# LandCruiser-Controller_1V1.net
KiCad netlist of a schematic drawn in EAGLE
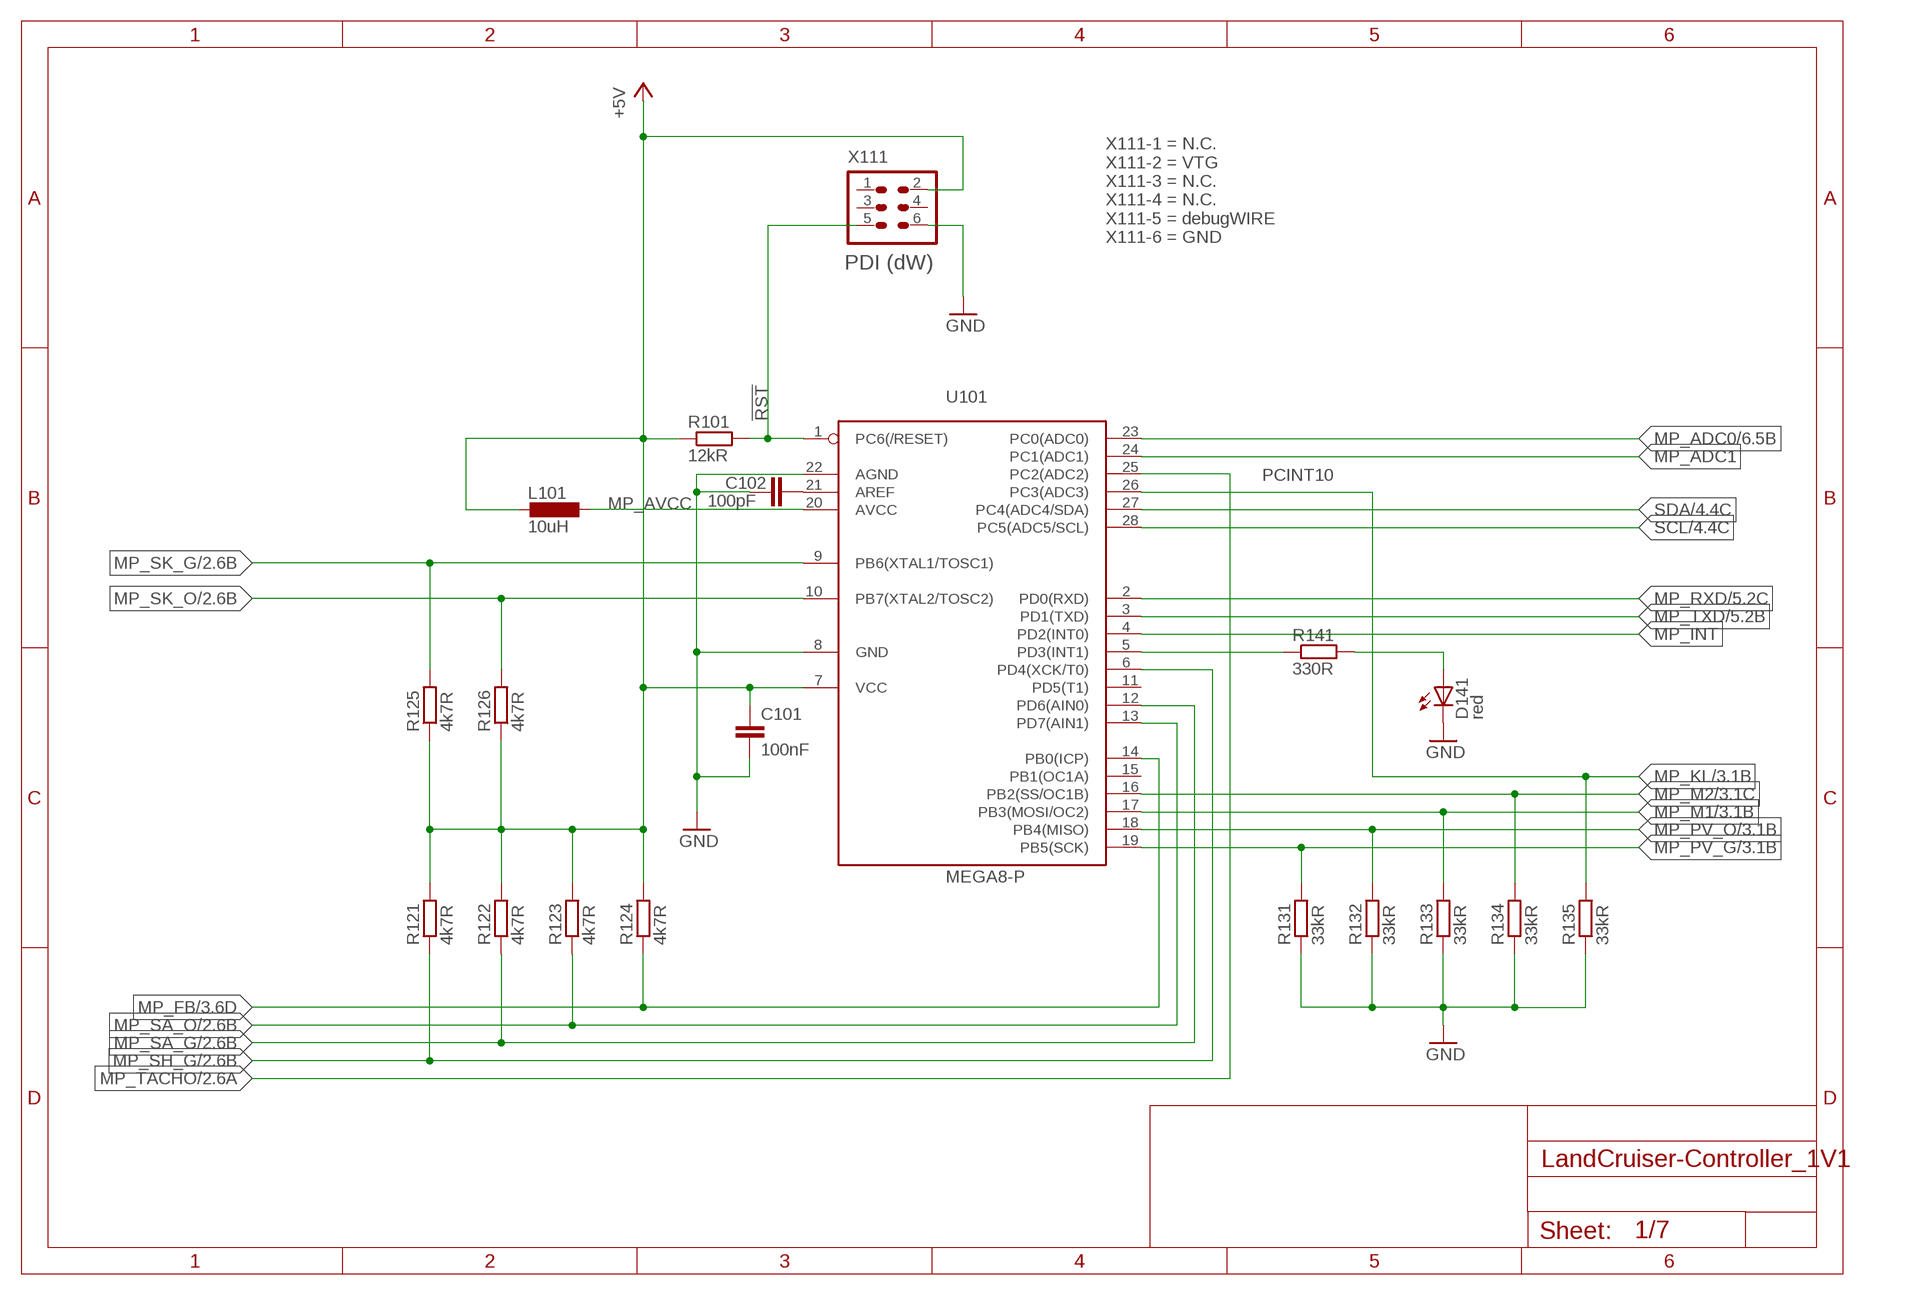
[diagram p0: schematic, sheet 1]
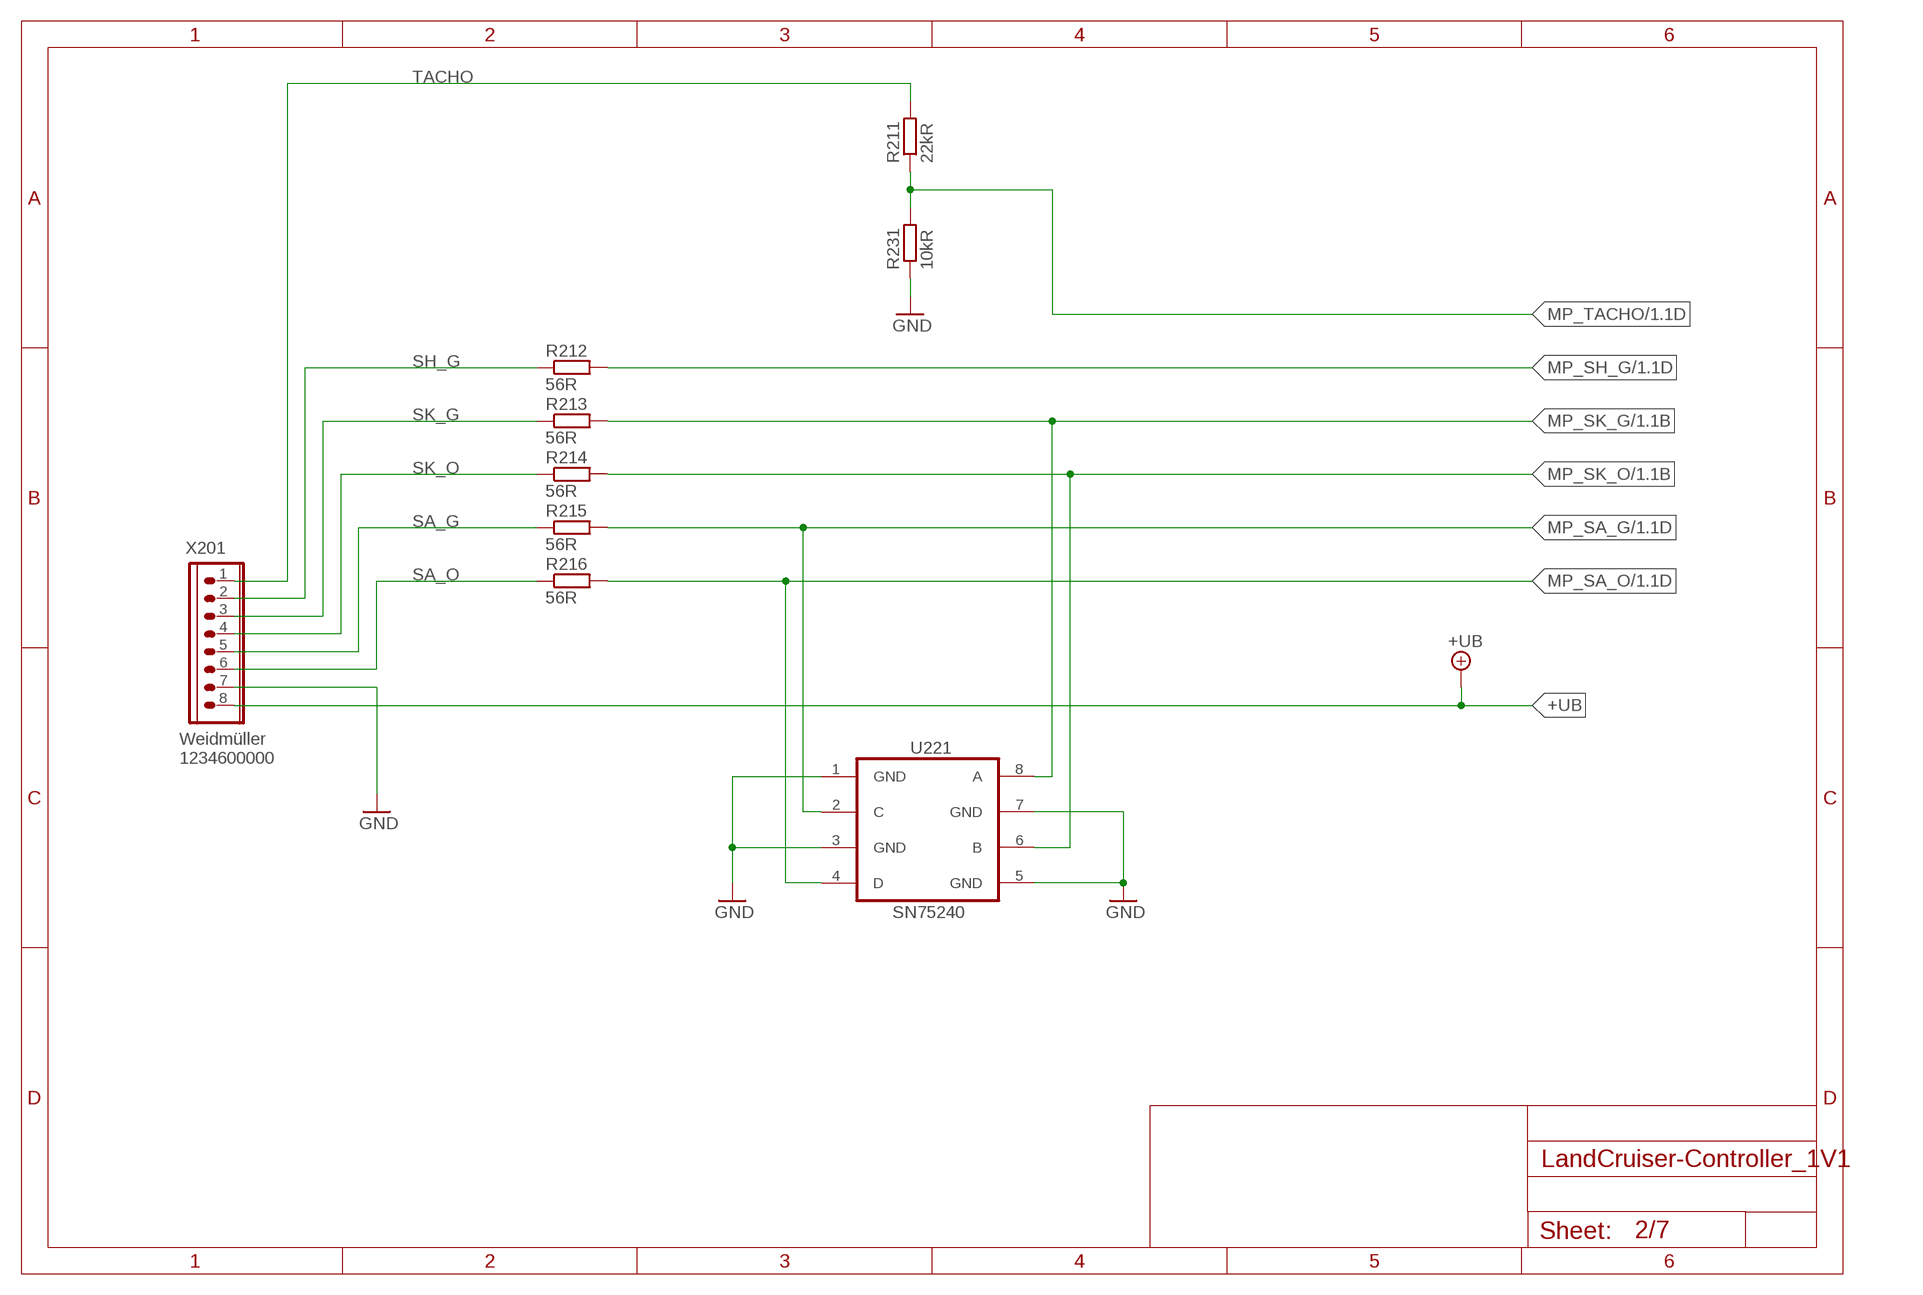
[diagram p1: schematic, sheet 2]
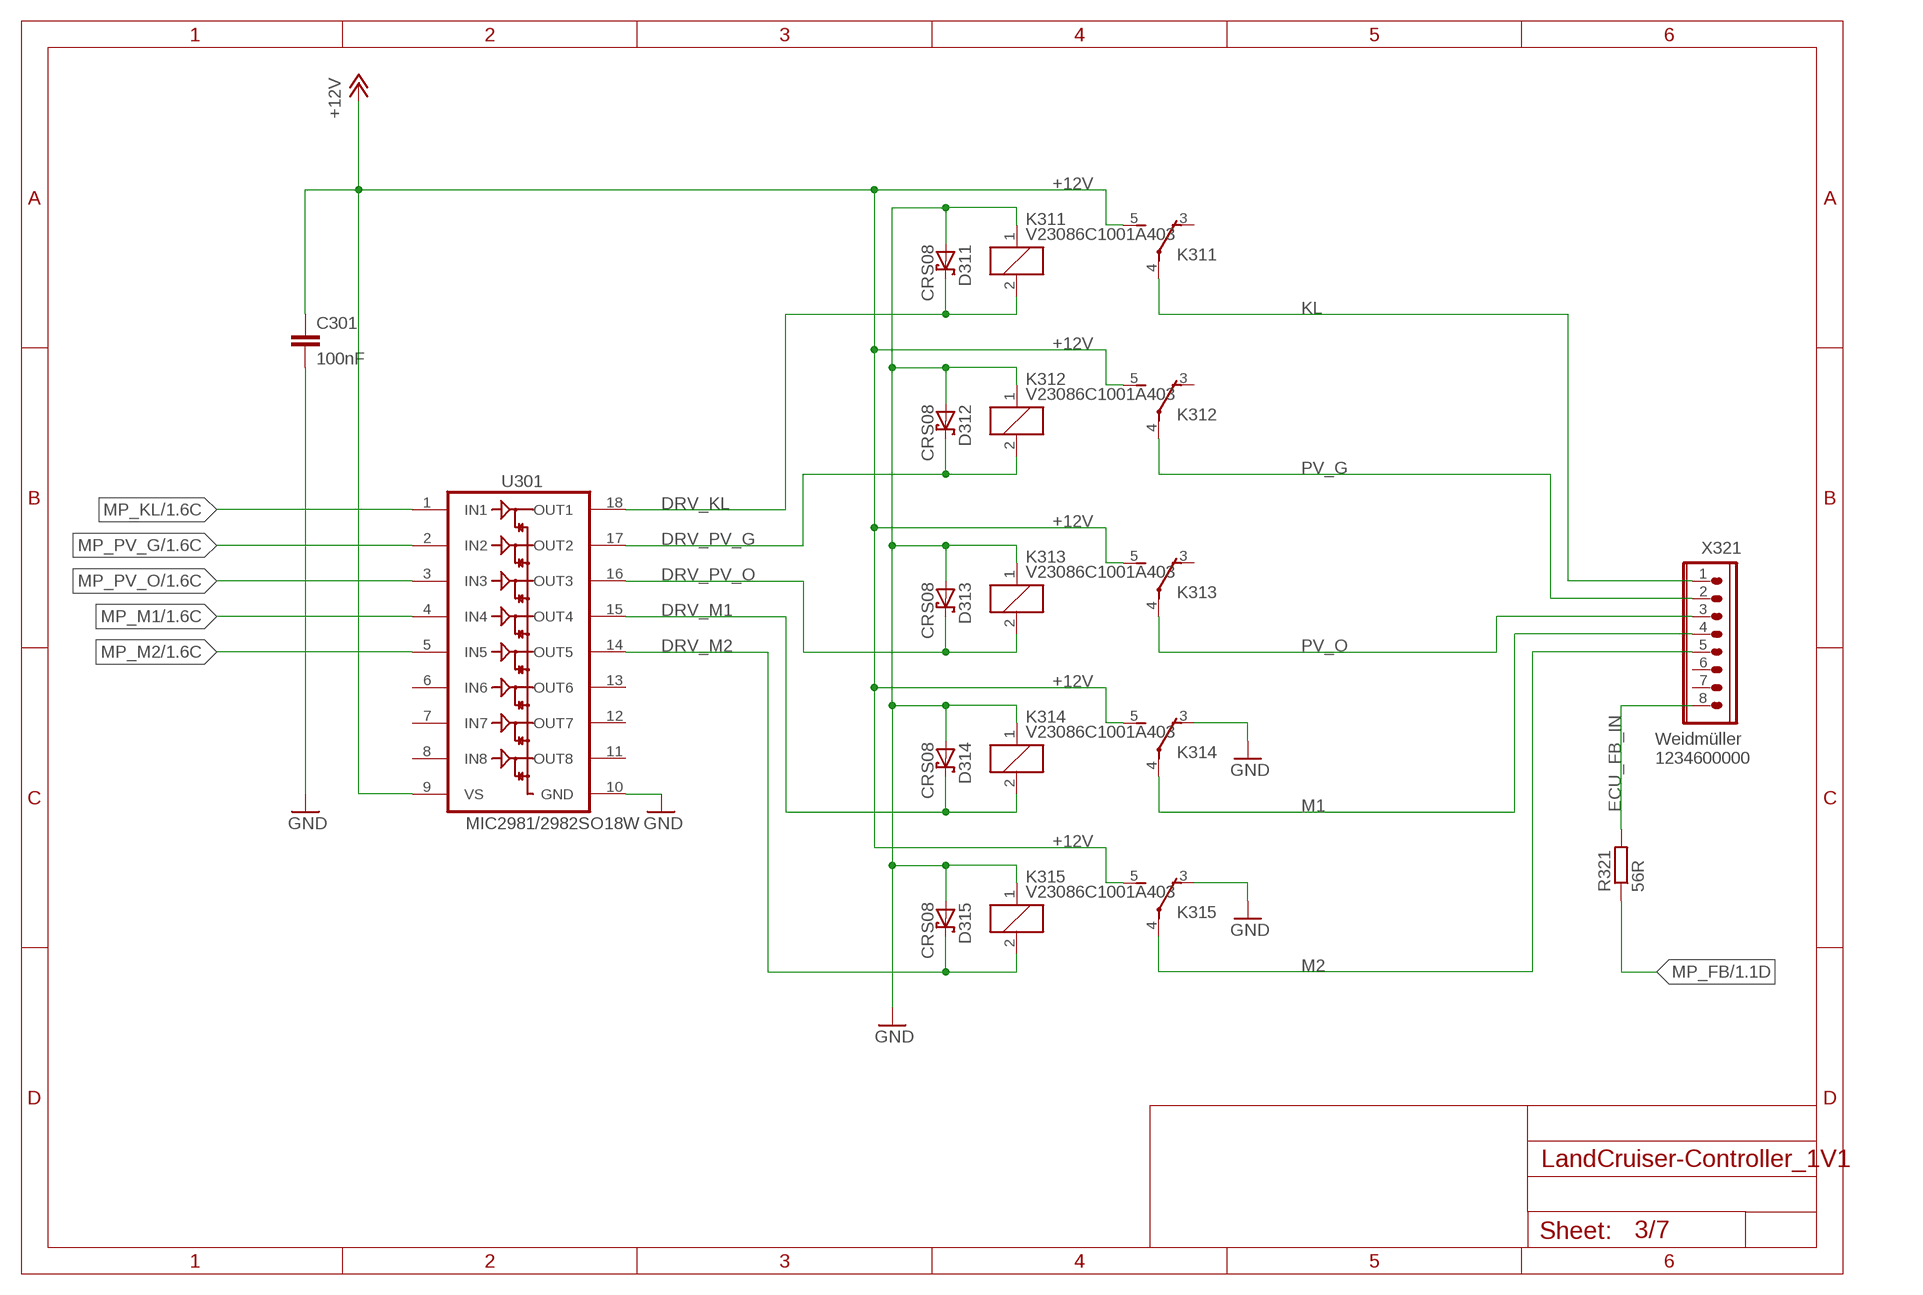
[diagram p2: schematic, sheet 3]
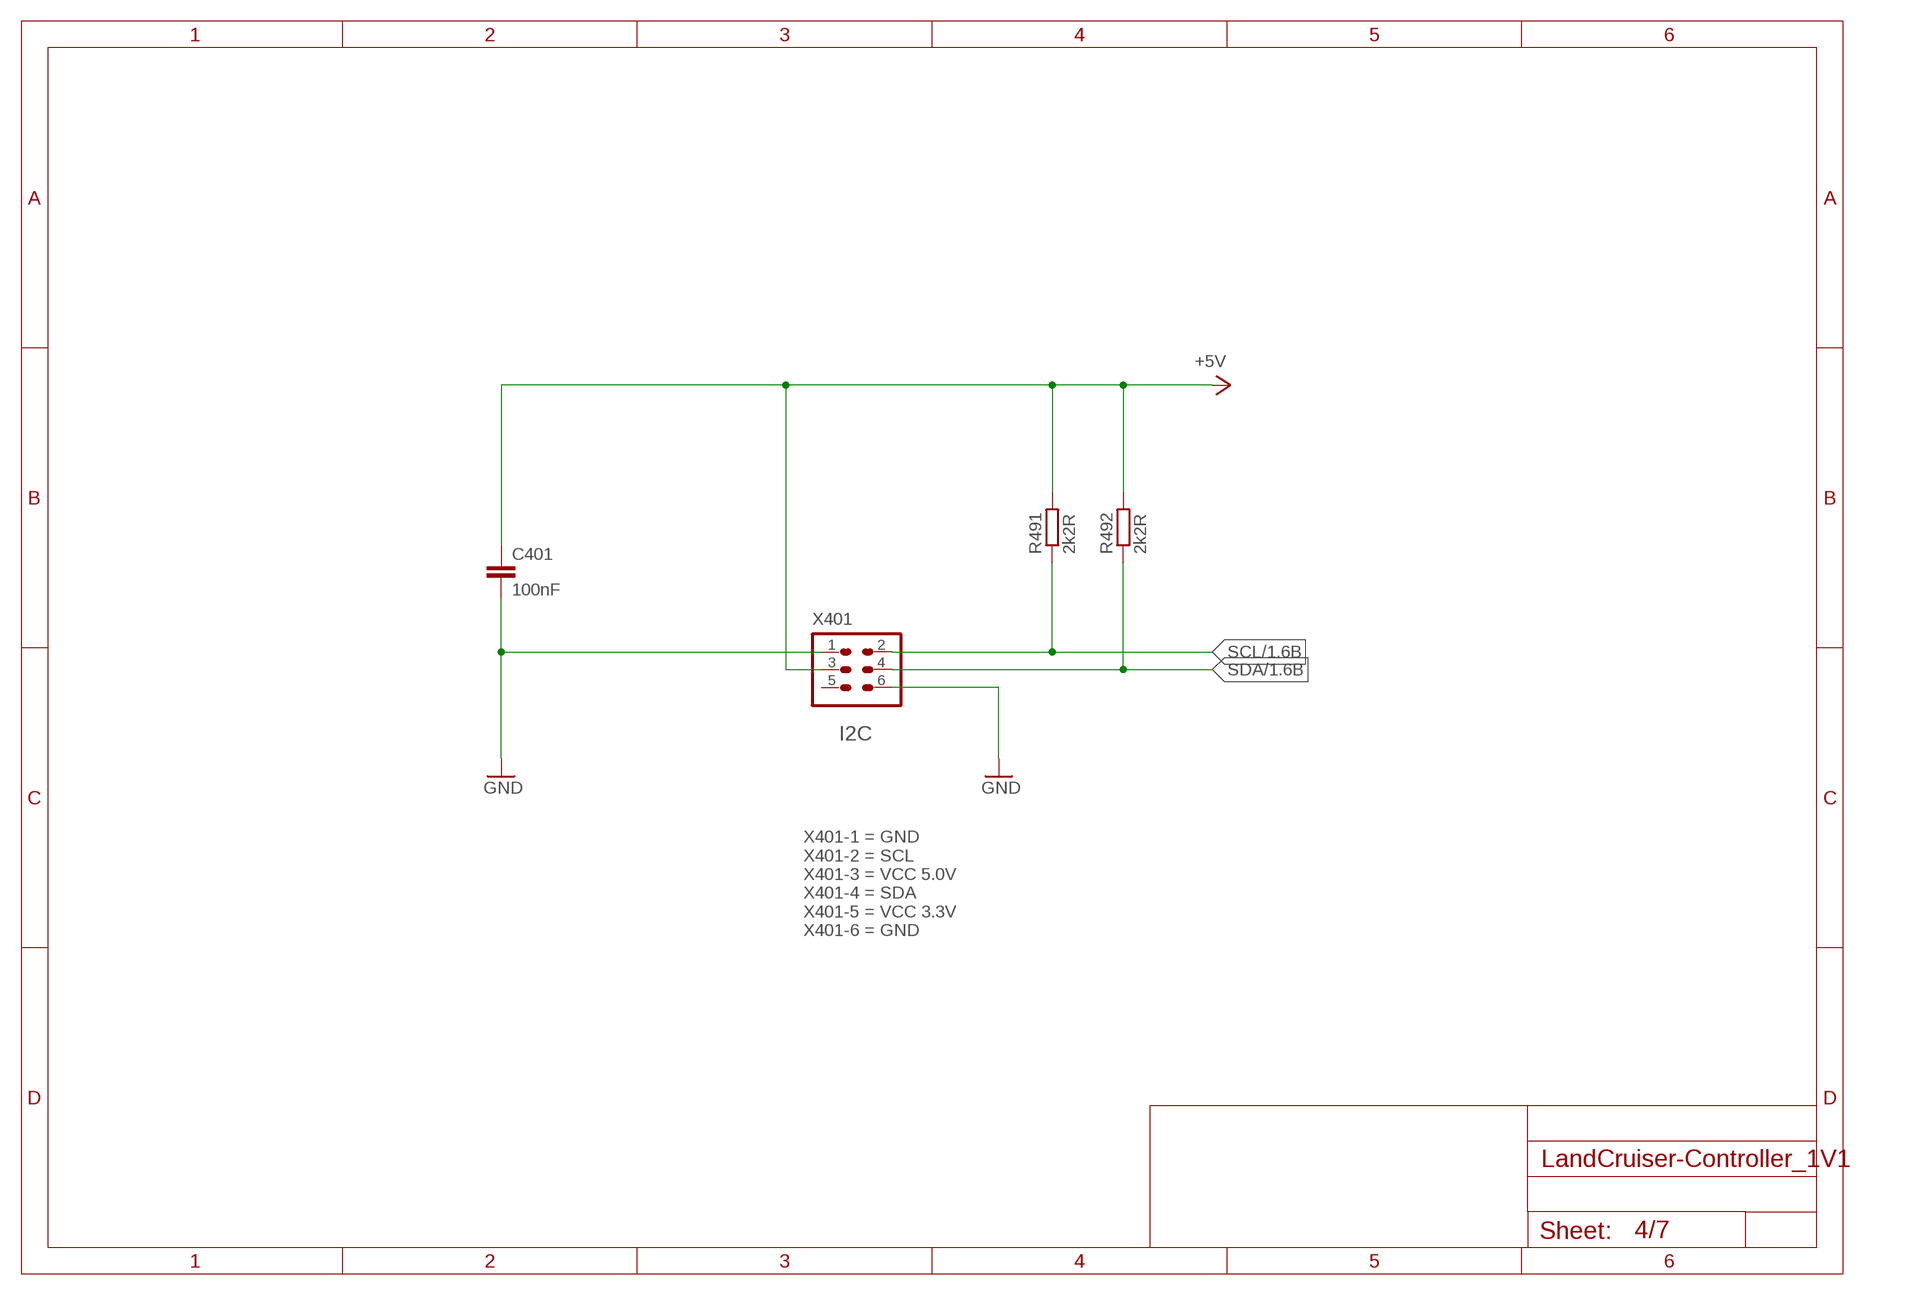
[diagram p3: schematic, sheet 4]
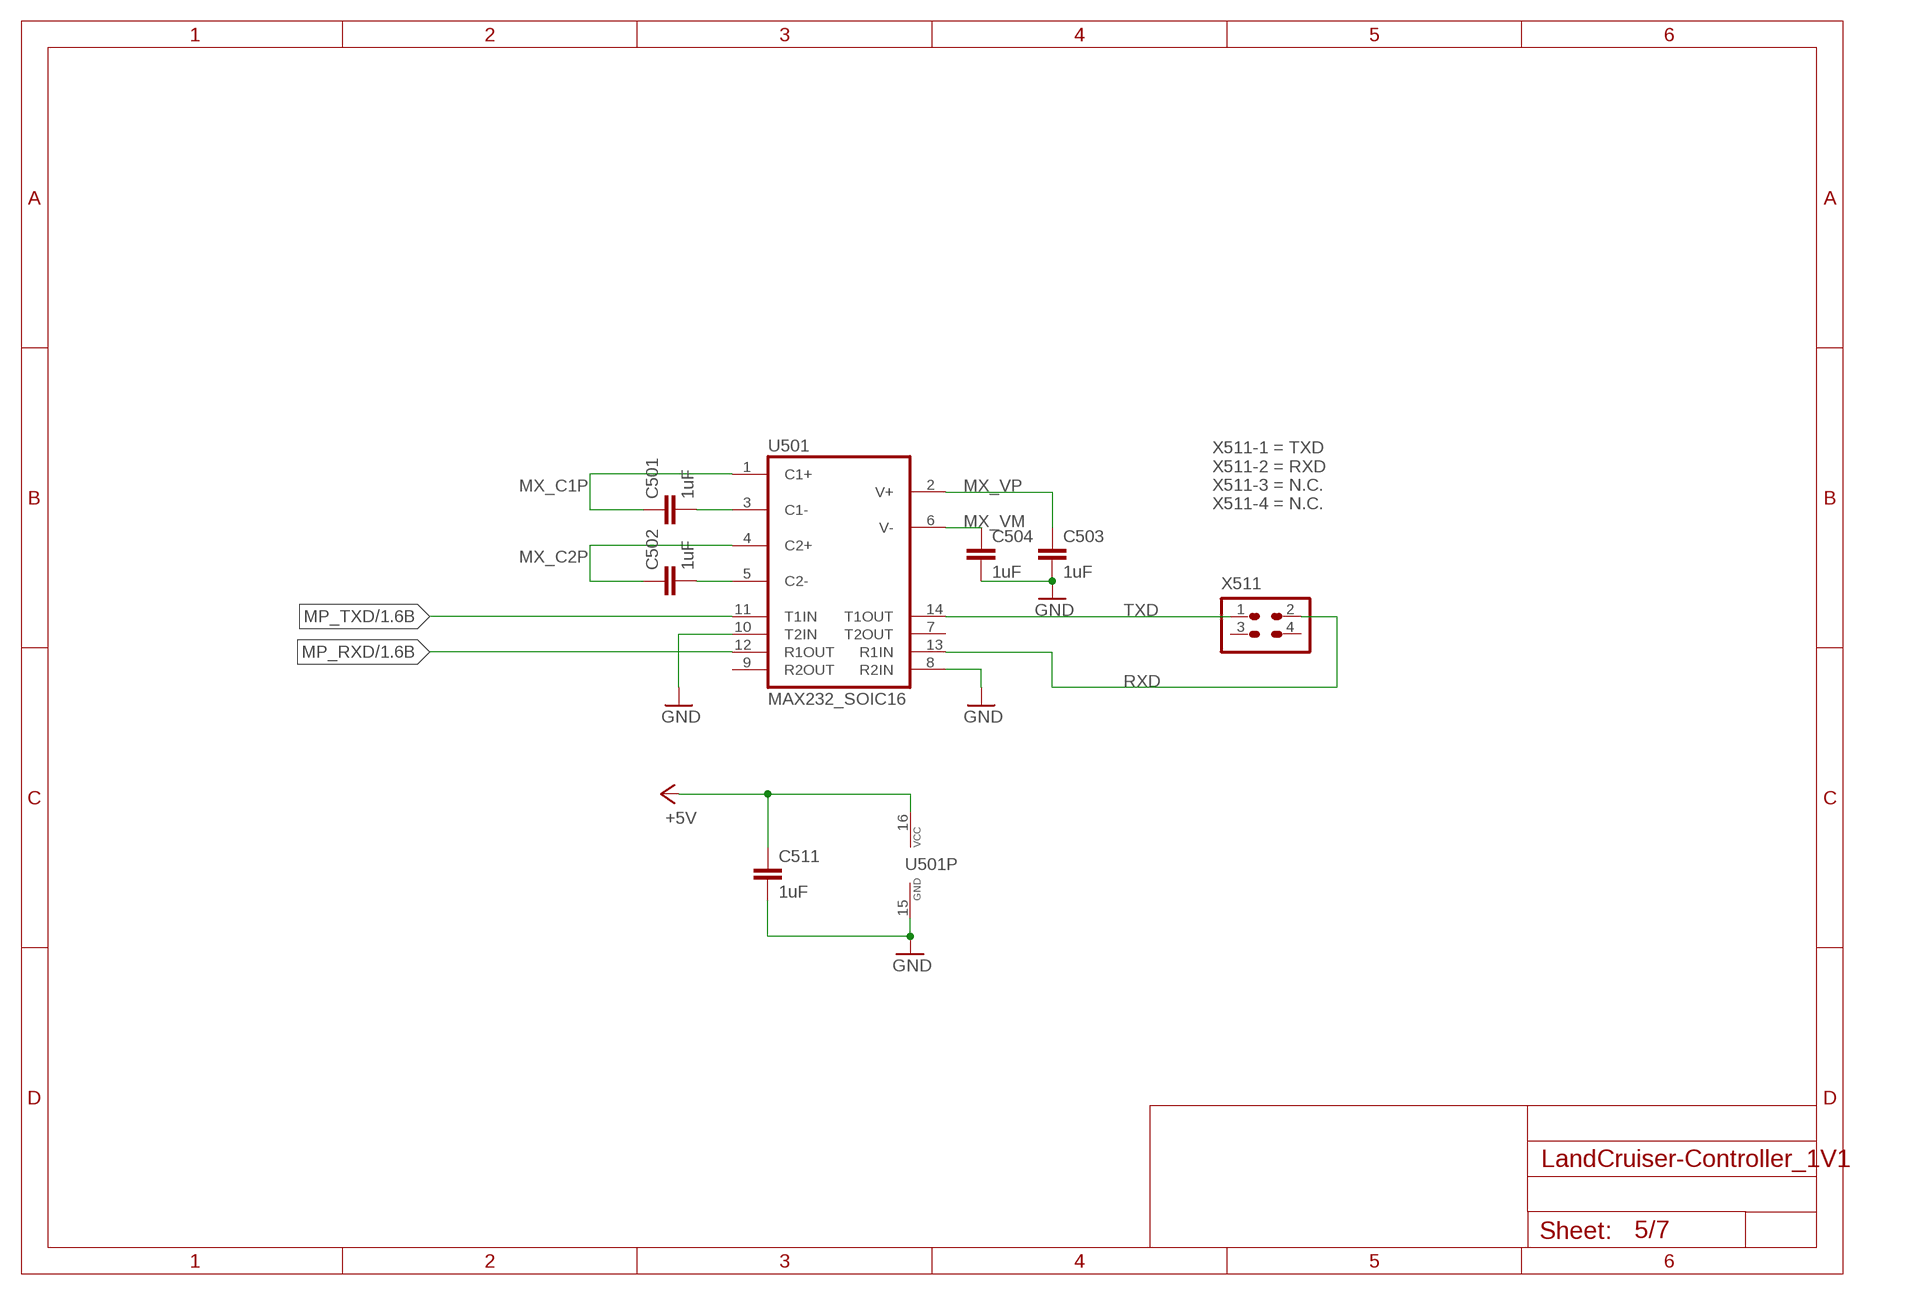
[diagram p4: schematic, sheet 5]
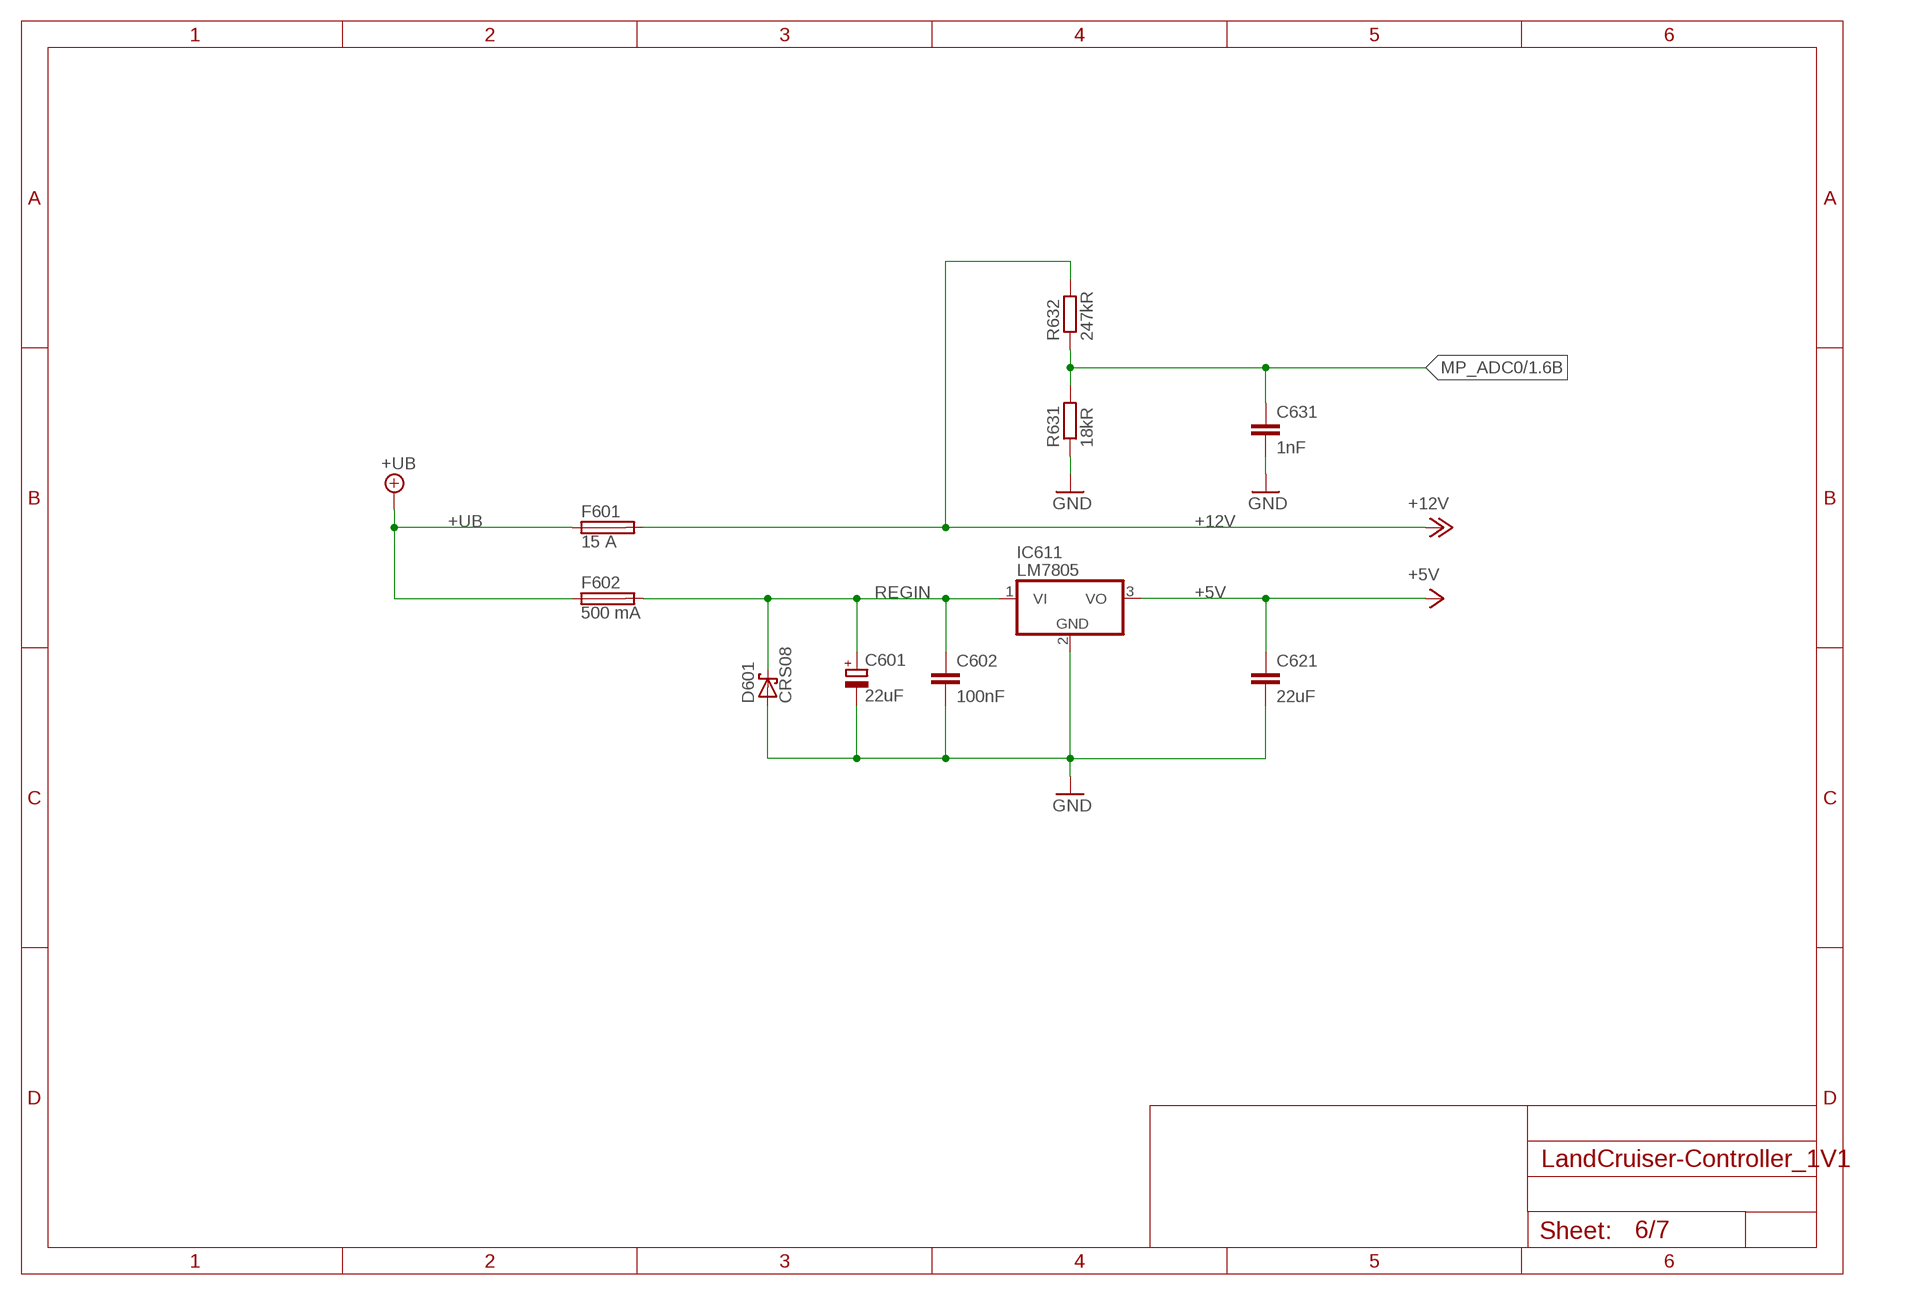
[diagram p5: schematic, sheet 6]
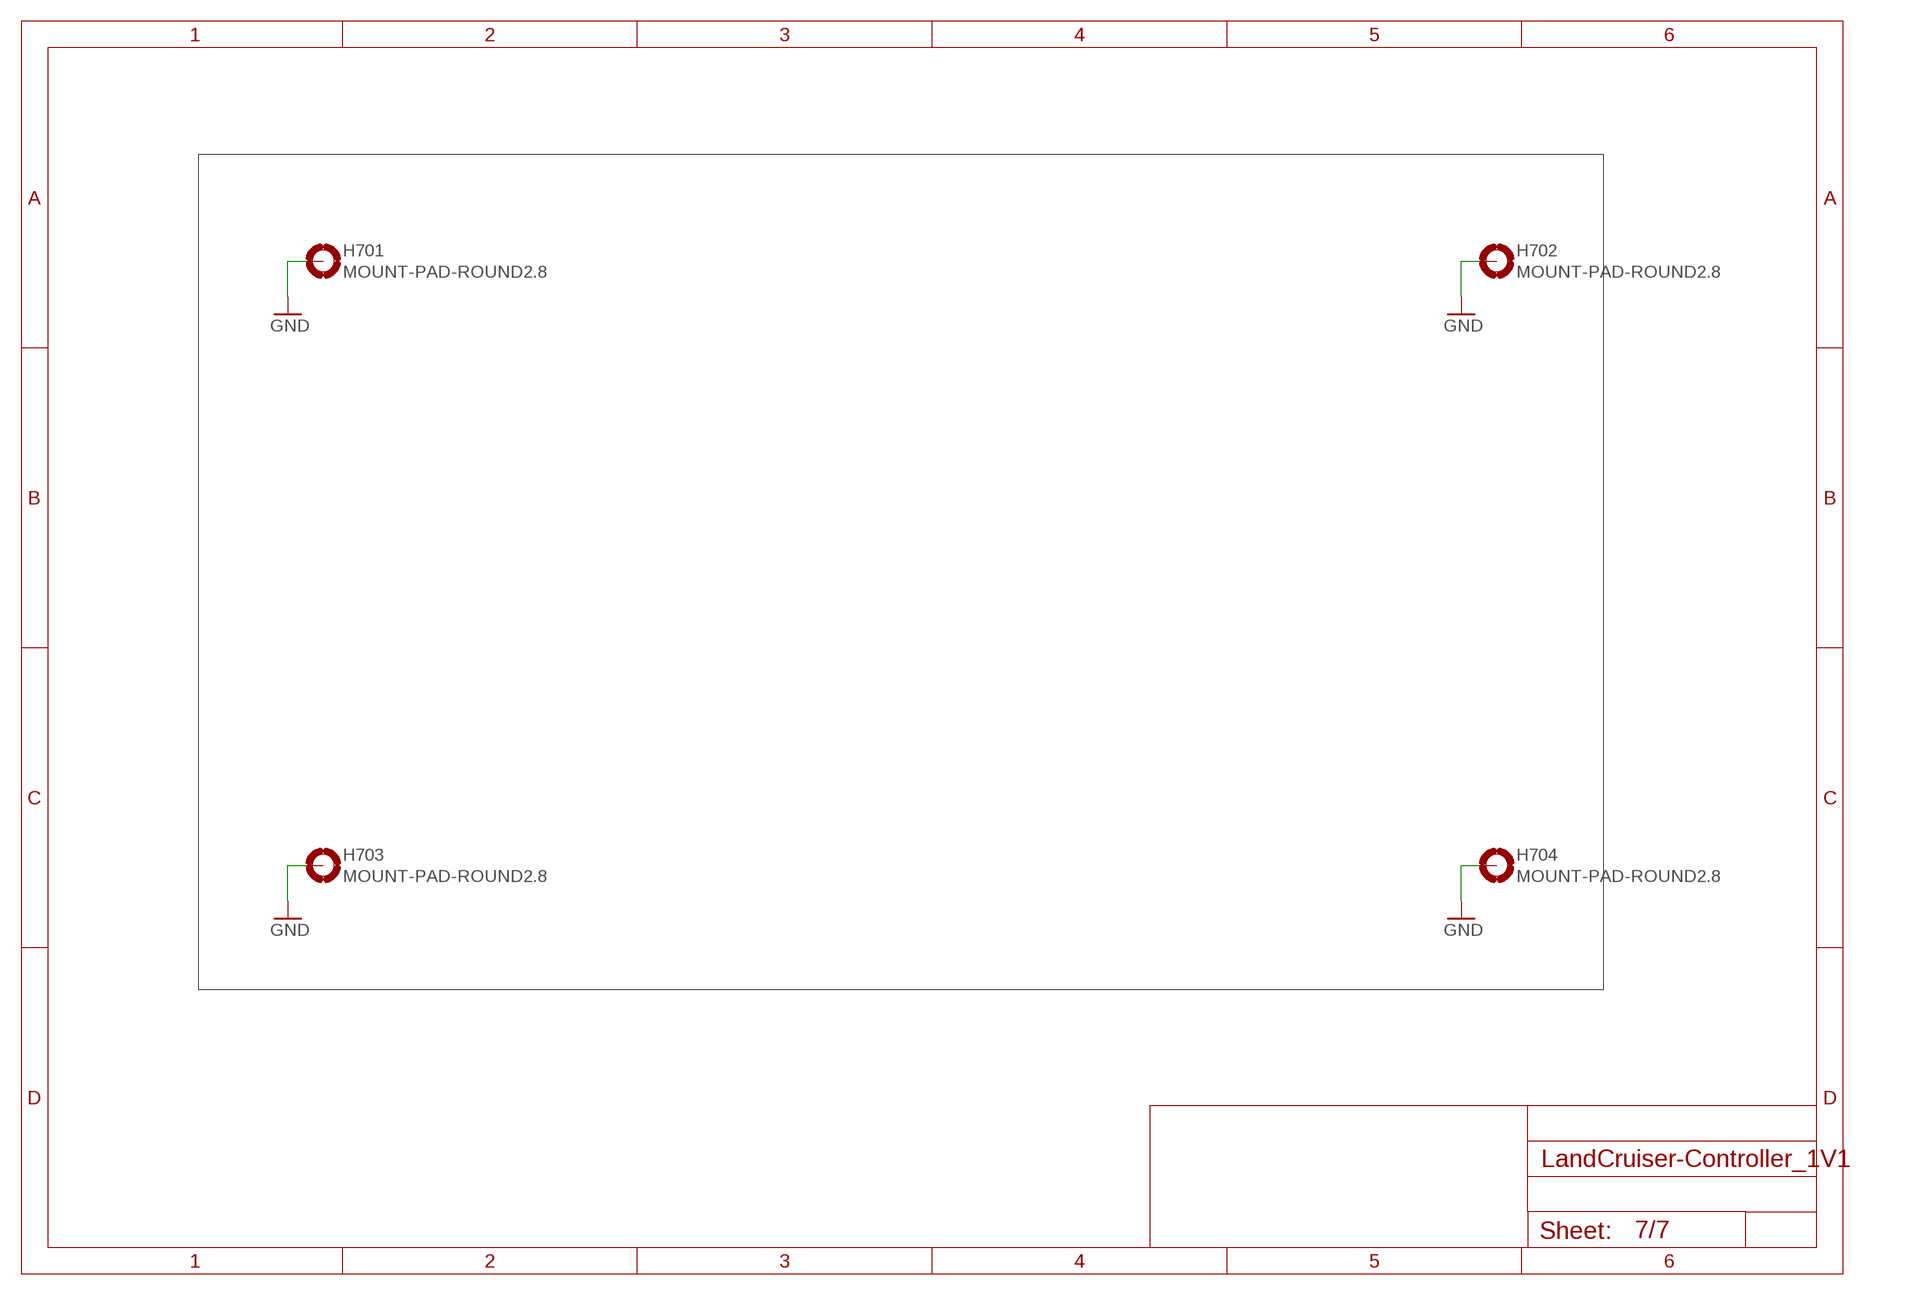
[diagram p6: schematic, sheet 7]

(export (version "E")
  (design (tool "Eeschema 10.0.6"))
  (components
    (comp (ref "C401")
      (value "100nF")
      (footprint "eagle-import:C0805")
      (libsource (lib "eagle-import") (part "C-EUC0805"))
    )
    (comp (ref "R491")
      (value "2k2R")
      (footprint "eagle-import:R0805")
      (libsource (lib "eagle-import") (part "R-EU_R0805"))
    )
    (comp (ref "R492")
      (value "2k2R")
      (footprint "eagle-import:R0805")
      (libsource (lib "eagle-import") (part "R-EU_R0805"))
    )
    (comp (ref "X401")
      (value "I2C")
      (footprint "eagle-import:2X03")
      (libsource (lib "eagle-import") (part "HEADER-2X3"))
    )
    (comp (ref "C301")
      (value "100nF")
      (footprint "eagle-import:C0805")
      (libsource (lib "eagle-import") (part "C-EUC0805"))
    )
    (comp (ref "D311")
      (value "CRS08")
      (footprint "eagle-import:SOD80C")
      (libsource (lib "eagle-import") (part "CRS08"))
    )
    (comp (ref "D312")
      (value "CRS08")
      (footprint "eagle-import:SOD80C")
      (libsource (lib "eagle-import") (part "CRS08"))
    )
    (comp (ref "D313")
      (value "CRS08")
      (footprint "eagle-import:SOD80C")
      (libsource (lib "eagle-import") (part "CRS08"))
    )
    (comp (ref "D314")
      (value "CRS08")
      (footprint "eagle-import:SOD80C")
      (libsource (lib "eagle-import") (part "CRS08"))
    )
    (comp (ref "D315")
      (value "CRS08")
      (footprint "eagle-import:SOD80C")
      (libsource (lib "eagle-import") (part "CRS08"))
    )
    (comp (ref "K311")
      (value "V23086C1001A403")
      (footprint "eagle-import:V23086-CO")
      (libsource (lib "eagle-import") (part "V23086C1001A403"))
    )
    (comp (ref "K312")
      (value "V23086C1001A403")
      (footprint "eagle-import:V23086-CO")
      (libsource (lib "eagle-import") (part "V23086C1001A403"))
    )
    (comp (ref "K313")
      (value "V23086C1001A403")
      (footprint "eagle-import:V23086-CO")
      (libsource (lib "eagle-import") (part "V23086C1001A403"))
    )
    (comp (ref "K314")
      (value "V23086C1001A403")
      (footprint "eagle-import:V23086-CO")
      (libsource (lib "eagle-import") (part "V23086C1001A403"))
    )
    (comp (ref "K315")
      (value "V23086C1001A403")
      (footprint "eagle-import:V23086-CO")
      (libsource (lib "eagle-import") (part "V23086C1001A403"))
    )
    (comp (ref "R321")
      (value "56R")
      (footprint "eagle-import:R0805")
      (libsource (lib "eagle-import") (part "R-EU_R0805"))
    )
    (comp (ref "U301")
      (value "MIC2981/2982SO18W")
      (footprint "eagle-import:SO-18W")
      (fields (field (name "MF") "MICROCHIP") (field (name "MP") "MIC2981/82YWM-TR"))
      (libsource (lib "eagle-import") (part "MIC2981/2982SO18W"))
    )
    (comp (ref "X321")
      (value "WEIDMUELLER 1234600000")
      (footprint "eagle-import:WIRE-TO-BOARD_5MM08_1X08")
      (libsource (lib "eagle-import") (part "WIRE-TO-BOARD_5MM08_1X08"))
    )
    (comp (ref "H701")
      (value "MOUNT-PAD-ROUND2.8")
      (footprint "eagle-import:2,8-PAD")
      (libsource (lib "eagle-import") (part "MOUNT-PAD-ROUND2.8"))
    )
    (comp (ref "H702")
      (value "MOUNT-PAD-ROUND2.8")
      (footprint "eagle-import:2,8-PAD")
      (libsource (lib "eagle-import") (part "MOUNT-PAD-ROUND2.8"))
    )
    (comp (ref "H703")
      (value "MOUNT-PAD-ROUND2.8")
      (footprint "eagle-import:2,8-PAD")
      (libsource (lib "eagle-import") (part "MOUNT-PAD-ROUND2.8"))
    )
    (comp (ref "H704")
      (value "MOUNT-PAD-ROUND2.8")
      (footprint "eagle-import:2,8-PAD")
      (libsource (lib "eagle-import") (part "MOUNT-PAD-ROUND2.8"))
    )
    (comp (ref "C501")
      (value "1uF")
      (footprint "eagle-import:C0805")
      (libsource (lib "eagle-import") (part "C-EUC0805"))
    )
    (comp (ref "C502")
      (value "1uF")
      (footprint "eagle-import:C0805")
      (libsource (lib "eagle-import") (part "C-EUC0805"))
    )
    (comp (ref "C503")
      (value "1uF")
      (footprint "eagle-import:C0805")
      (libsource (lib "eagle-import") (part "C-EUC0805"))
    )
    (comp (ref "C504")
      (value "1uF")
      (footprint "eagle-import:C0805")
      (libsource (lib "eagle-import") (part "C-EUC0805"))
    )
    (comp (ref "C511")
      (value "1uF")
      (footprint "eagle-import:C0805")
      (libsource (lib "eagle-import") (part "C-EUC0805"))
    )
    (comp (ref "U501")
      (value "MAX232_SOIC16")
      (footprint "eagle-import:SOIC16N")
      (fields (field (name "MF") "MAXIM") (field (name "MPN") "MAX232ECDR"))
      (libsource (lib "eagle-import") (part "MAX232_SOIC16"))
    )
    (comp (ref "X511")
      (value "HEADER-2X2")
      (footprint "eagle-import:2X02")
      (libsource (lib "eagle-import") (part "HEADER-2X2"))
    )
    (comp (ref "R211")
      (value "22kR")
      (footprint "eagle-import:R0805")
      (libsource (lib "eagle-import") (part "R-EU_R0805"))
    )
    (comp (ref "R212")
      (value "56R")
      (footprint "eagle-import:R0805")
      (libsource (lib "eagle-import") (part "R-EU_R0805"))
    )
    (comp (ref "R213")
      (value "56R")
      (footprint "eagle-import:R0805")
      (libsource (lib "eagle-import") (part "R-EU_R0805"))
    )
    (comp (ref "R214")
      (value "56R")
      (footprint "eagle-import:R0805")
      (libsource (lib "eagle-import") (part "R-EU_R0805"))
    )
    (comp (ref "R215")
      (value "56R")
      (footprint "eagle-import:R0805")
      (libsource (lib "eagle-import") (part "R-EU_R0805"))
    )
    (comp (ref "R216")
      (value "56R")
      (footprint "eagle-import:R0805")
      (libsource (lib "eagle-import") (part "R-EU_R0805"))
    )
    (comp (ref "R231")
      (value "10kR")
      (footprint "eagle-import:R0805")
      (libsource (lib "eagle-import") (part "R-EU_R0805"))
    )
    (comp (ref "U221")
      (value "SN75240")
      (footprint "eagle-import:TSSOP-8")
      (libsource (lib "eagle-import") (part "SN75240"))
    )
    (comp (ref "X201")
      (value "WEIDMUELLER 1234600000")
      (footprint "eagle-import:WIRE-TO-BOARD_5MM08_1X08")
      (libsource (lib "eagle-import") (part "WIRE-TO-BOARD_5MM08_1X08"))
    )
    (comp (ref "C101")
      (value "100nF")
      (footprint "eagle-import:C0805")
      (libsource (lib "eagle-import") (part "C-EUC0805"))
    )
    (comp (ref "C102")
      (value "100pF")
      (footprint "eagle-import:C0805")
      (libsource (lib "eagle-import") (part "C-EUC0805"))
    )
    (comp (ref "D141")
      (value "red")
      (footprint "eagle-import:LED_2PIN-TTH")
      (libsource (lib "eagle-import") (part "LED"))
    )
    (comp (ref "L101")
      (value "10uH")
      (footprint "eagle-import:L1812")
      (libsource (lib "eagle-import") (part "L-EUL1812"))
    )
    (comp (ref "R101")
      (value "12kR")
      (footprint "eagle-import:R0805")
      (libsource (lib "eagle-import") (part "R-EU_R0805"))
    )
    (comp (ref "R121")
      (value "4k7R")
      (footprint "eagle-import:R0805")
      (libsource (lib "eagle-import") (part "R-EU_R0805"))
    )
    (comp (ref "R122")
      (value "4k7R")
      (footprint "eagle-import:R0805")
      (libsource (lib "eagle-import") (part "R-EU_R0805"))
    )
    (comp (ref "R123")
      (value "4k7R")
      (footprint "eagle-import:R0805")
      (libsource (lib "eagle-import") (part "R-EU_R0805"))
    )
    (comp (ref "R124")
      (value "4k7R")
      (footprint "eagle-import:R0805")
      (libsource (lib "eagle-import") (part "R-EU_R0805"))
    )
    (comp (ref "R125")
      (value "4k7R")
      (footprint "eagle-import:R0805")
      (libsource (lib "eagle-import") (part "R-EU_R0805"))
    )
    (comp (ref "R126")
      (value "4k7R")
      (footprint "eagle-import:R0805")
      (libsource (lib "eagle-import") (part "R-EU_R0805"))
    )
    (comp (ref "R131")
      (value "33kR")
      (footprint "eagle-import:R0805")
      (libsource (lib "eagle-import") (part "R-EU_R0805"))
    )
    (comp (ref "R132")
      (value "33kR")
      (footprint "eagle-import:R0805")
      (libsource (lib "eagle-import") (part "R-EU_R0805"))
    )
    (comp (ref "R133")
      (value "33kR")
      (footprint "eagle-import:R0805")
      (libsource (lib "eagle-import") (part "R-EU_R0805"))
    )
    (comp (ref "R134")
      (value "33kR")
      (footprint "eagle-import:R0805")
      (libsource (lib "eagle-import") (part "R-EU_R0805"))
    )
    (comp (ref "R135")
      (value "33kR")
      (footprint "eagle-import:R0805")
      (libsource (lib "eagle-import") (part "R-EU_R0805"))
    )
    (comp (ref "R141")
      (value "330R")
      (footprint "eagle-import:R0805")
      (libsource (lib "eagle-import") (part "R-EU_R0805"))
    )
    (comp (ref "U101")
      (value "MEGA8-P")
      (footprint "eagle-import:DIL28-3")
      (libsource (lib "eagle-import") (part "MEGA8-P"))
    )
    (comp (ref "X111")
      (value "HEADER-2X3")
      (footprint "eagle-import:2X03")
      (libsource (lib "eagle-import") (part "HEADER-2X3"))
    )
    (comp (ref "C601")
      (value "22uF")
      (footprint "eagle-import:E2,5-7")
      (libsource (lib "eagle-import") (part "CPOL-EUE2.5-7"))
    )
    (comp (ref "C602")
      (value "100nF")
      (footprint "eagle-import:C0805")
      (libsource (lib "eagle-import") (part "C-EUC0805"))
    )
    (comp (ref "C621")
      (value "22uF")
      (footprint "eagle-import:C0805")
      (libsource (lib "eagle-import") (part "C-EUC0805"))
    )
    (comp (ref "C631")
      (value "1nF")
      (footprint "eagle-import:C0805")
      (libsource (lib "eagle-import") (part "C-EUC0805"))
    )
    (comp (ref "D601")
      (value "CRS08")
      (footprint "eagle-import:SOD80C")
      (libsource (lib "eagle-import") (part "CRS08"))
    )
    (comp (ref "F601")
      (value "15 A")
      (footprint "eagle-import:MCCQ-121")
      (fields (field (name "MF") "MINICOMP") (field (name "MPN") "MCCQ-121"))
      (libsource (lib "eagle-import") (part "MCCQ-121"))
    )
    (comp (ref "F602")
      (value "500 mA")
      (footprint "eagle-import:MCCQ-121")
      (fields (field (name "MF") "MINICOMP") (field (name "MPN") "MCCQ-121"))
      (libsource (lib "eagle-import") (part "MCCQ-121"))
    )
    (comp (ref "IC611")
      (value "LM7805")
      (footprint "eagle-import:TO220H")
      (libsource (lib "eagle-import") (part "78T05"))
    )
    (comp (ref "R631")
      (value "18kR")
      (footprint "eagle-import:R0805")
      (libsource (lib "eagle-import") (part "R-EU_R0805"))
    )
    (comp (ref "R632")
      (value "247kR")
      (footprint "eagle-import:R0805")
      (libsource (lib "eagle-import") (part "R-EU_R0805"))
    )
  )
  (nets
    (net (code "1") (name "+5V") (class "Default")
      (node (ref "C101") (pin "1") (pinfunction "1_1") (pintype "passive"))
      (node (ref "C401") (pin "1") (pinfunction "1_1") (pintype "passive"))
      (node (ref "C511") (pin "1") (pinfunction "1_1") (pintype "passive"))
      (node (ref "C621") (pin "1") (pinfunction "1_1") (pintype "passive"))
      (node (ref "IC611") (pin "3") (pinfunction "VO_3") (pintype "passive"))
      (node (ref "L101") (pin "2") (pinfunction "2_2") (pintype "passive"))
      (node (ref "R101") (pin "1") (pinfunction "1_1") (pintype "passive"))
      (node (ref "R121") (pin "2") (pinfunction "2_2") (pintype "passive"))
      (node (ref "R122") (pin "2") (pinfunction "2_2") (pintype "passive"))
      (node (ref "R123") (pin "2") (pinfunction "2_2") (pintype "passive"))
      (node (ref "R124") (pin "2") (pinfunction "2_2") (pintype "passive"))
      (node (ref "R125") (pin "1") (pinfunction "1_1") (pintype "passive"))
      (node (ref "R126") (pin "1") (pinfunction "1_1") (pintype "passive"))
      (node (ref "R491") (pin "2") (pinfunction "2_2") (pintype "passive"))
      (node (ref "R492") (pin "2") (pinfunction "2_2") (pintype "passive"))
      (node (ref "U101") (pin "7") (pinfunction "VCC_7") (pintype "bidirectional"))
      (node (ref "U501") (pin "16") (pinfunction "VCC_16") (pintype "power_in"))
      (node (ref "X111") (pin "2") (pinfunction "2_2") (pintype "passive"))
      (node (ref "X401") (pin "3") (pinfunction "3_3") (pintype "passive"))
    )
    (net (code "2") (name "+12V") (class "Default")
      (node (ref "C301") (pin "1") (pinfunction "1_1") (pintype "passive"))
      (node (ref "F601") (pin "3") (pinfunction "2_3") (pintype "passive"))
      (node (ref "F601") (pin "4") (pinfunction "2_4") (pintype "passive"))
      (node (ref "K311") (pin "5") (pinfunction "S_5") (pintype "passive"))
      (node (ref "K312") (pin "5") (pinfunction "S_5") (pintype "passive"))
      (node (ref "K313") (pin "5") (pinfunction "S_5") (pintype "passive"))
      (node (ref "K314") (pin "5") (pinfunction "S_5") (pintype "passive"))
      (node (ref "K315") (pin "5") (pinfunction "S_5") (pintype "passive"))
      (node (ref "R632") (pin "2") (pinfunction "2_2") (pintype "passive"))
      (node (ref "U301") (pin "9") (pinfunction "VS_9") (pintype "power_in"))
    )
    (net (code "3") (name "+UB") (class "Default")
      (node (ref "F601") (pin "1") (pinfunction "1_1") (pintype "passive"))
      (node (ref "F601") (pin "2") (pinfunction "1_2") (pintype "passive"))
      (node (ref "F602") (pin "1") (pinfunction "1_1") (pintype "passive"))
      (node (ref "F602") (pin "2") (pinfunction "1_2") (pintype "passive"))
      (node (ref "X201") (pin "8") (pinfunction "8_8") (pintype "passive"))
    )
    (net (code "4") (name "DRV_KL") (class "Default")
      (node (ref "D311") (pin "C") (pinfunction "C_C") (pintype "passive"))
      (node (ref "K311") (pin "2") (pinfunction "2_2") (pintype "passive"))
      (node (ref "U301") (pin "18") (pinfunction "OUT1_18") (pintype "open_collector"))
    )
    (net (code "5") (name "DRV_M1") (class "Default")
      (node (ref "D314") (pin "C") (pinfunction "C_C") (pintype "passive"))
      (node (ref "K314") (pin "2") (pinfunction "2_2") (pintype "passive"))
      (node (ref "U301") (pin "15") (pinfunction "OUT4_15") (pintype "open_collector"))
    )
    (net (code "6") (name "DRV_M2") (class "Default")
      (node (ref "D315") (pin "C") (pinfunction "C_C") (pintype "passive"))
      (node (ref "K315") (pin "2") (pinfunction "2_2") (pintype "passive"))
      (node (ref "U301") (pin "14") (pinfunction "OUT5_14") (pintype "open_collector"))
    )
    (net (code "7") (name "DRV_PV_G") (class "Default")
      (node (ref "D312") (pin "C") (pinfunction "C_C") (pintype "passive"))
      (node (ref "K312") (pin "2") (pinfunction "2_2") (pintype "passive"))
      (node (ref "U301") (pin "17") (pinfunction "OUT2_17") (pintype "open_collector"))
    )
    (net (code "8") (name "DRV_PV_O") (class "Default")
      (node (ref "D313") (pin "C") (pinfunction "C_C") (pintype "passive"))
      (node (ref "K313") (pin "2") (pinfunction "2_2") (pintype "passive"))
      (node (ref "U301") (pin "16") (pinfunction "OUT3_16") (pintype "open_collector"))
    )
    (net (code "9") (name "ECU_FB_IN") (class "Default")
      (node (ref "R321") (pin "2") (pinfunction "2_2") (pintype "passive"))
      (node (ref "X321") (pin "8") (pinfunction "8_8") (pintype "passive"))
    )
    (net (code "10") (name "GND") (class "Default")
      (node (ref "C101") (pin "2") (pinfunction "2_2") (pintype "passive"))
      (node (ref "C102") (pin "1") (pinfunction "1_1") (pintype "passive"))
      (node (ref "C301") (pin "2") (pinfunction "2_2") (pintype "passive"))
      (node (ref "C401") (pin "2") (pinfunction "2_2") (pintype "passive"))
      (node (ref "C503") (pin "2") (pinfunction "2_2") (pintype "passive"))
      (node (ref "C504") (pin "2") (pinfunction "2_2") (pintype "passive"))
      (node (ref "C511") (pin "2") (pinfunction "2_2") (pintype "passive"))
      (node (ref "C601") (pin "-") (pinfunction "-_-") (pintype "passive"))
      (node (ref "C602") (pin "2") (pinfunction "2_2") (pintype "passive"))
      (node (ref "C621") (pin "2") (pinfunction "2_2") (pintype "passive"))
      (node (ref "C631") (pin "2") (pinfunction "2_2") (pintype "passive"))
      (node (ref "D141") (pin "C") (pinfunction "C_C") (pintype "passive"))
      (node (ref "D311") (pin "A") (pinfunction "A_A") (pintype "passive"))
      (node (ref "D312") (pin "A") (pinfunction "A_A") (pintype "passive"))
      (node (ref "D313") (pin "A") (pinfunction "A_A") (pintype "passive"))
      (node (ref "D314") (pin "A") (pinfunction "A_A") (pintype "passive"))
      (node (ref "D315") (pin "A") (pinfunction "A_A") (pintype "passive"))
      (node (ref "D601") (pin "A") (pinfunction "A_A") (pintype "passive"))
      (node (ref "H701") (pin "B2,8") (pinfunction "MOUNT_B2,8") (pintype "passive"))
      (node (ref "H702") (pin "B2,8") (pinfunction "MOUNT_B2,8") (pintype "passive"))
      (node (ref "H703") (pin "B2,8") (pinfunction "MOUNT_B2,8") (pintype "passive"))
      (node (ref "H704") (pin "B2,8") (pinfunction "MOUNT_B2,8") (pintype "passive"))
      (node (ref "IC611") (pin "2") (pinfunction "GND_2") (pintype "passive"))
      (node (ref "K311") (pin "1") (pinfunction "1_1") (pintype "passive"))
      (node (ref "K312") (pin "1") (pinfunction "1_1") (pintype "passive"))
      (node (ref "K313") (pin "1") (pinfunction "1_1") (pintype "passive"))
      (node (ref "K314") (pin "1") (pinfunction "1_1") (pintype "passive"))
      (node (ref "K314") (pin "3") (pinfunction "O_3") (pintype "passive"))
      (node (ref "K315") (pin "1") (pinfunction "1_1") (pintype "passive"))
      (node (ref "K315") (pin "3") (pinfunction "O_3") (pintype "passive"))
      (node (ref "R131") (pin "1") (pinfunction "1_1") (pintype "passive"))
      (node (ref "R132") (pin "1") (pinfunction "1_1") (pintype "passive"))
      (node (ref "R133") (pin "1") (pinfunction "1_1") (pintype "passive"))
      (node (ref "R134") (pin "1") (pinfunction "1_1") (pintype "passive"))
      (node (ref "R135") (pin "1") (pinfunction "1_1") (pintype "passive"))
      (node (ref "R231") (pin "1") (pinfunction "1_1") (pintype "passive"))
      (node (ref "R631") (pin "1") (pinfunction "1_1") (pintype "passive"))
      (node (ref "U101") (pin "22") (pinfunction "AGND_22") (pintype "bidirectional"))
      (node (ref "U101") (pin "8") (pinfunction "GND_8") (pintype "bidirectional"))
      (node (ref "U221") (pin "1") (pinfunction "GND_1") (pintype "power_in"))
      (node (ref "U221") (pin "3") (pinfunction "GND_3") (pintype "power_in"))
      (node (ref "U221") (pin "5") (pinfunction "GND_5") (pintype "power_in"))
      (node (ref "U221") (pin "7") (pinfunction "GND_7") (pintype "power_in"))
      (node (ref "U301") (pin "10") (pinfunction "GND_10") (pintype "power_in"))
      (node (ref "U501") (pin "10") (pinfunction "T2IN_10") (pintype "input"))
      (node (ref "U501") (pin "15") (pinfunction "GND_15") (pintype "power_in"))
      (node (ref "U501") (pin "8") (pinfunction "R2IN_8") (pintype "input"))
      (node (ref "X111") (pin "6") (pinfunction "6_6") (pintype "passive"))
      (node (ref "X201") (pin "7") (pinfunction "7_7") (pintype "passive"))
      (node (ref "X401") (pin "1") (pinfunction "1_1") (pintype "passive"))
      (node (ref "X401") (pin "6") (pinfunction "6_6") (pintype "passive"))
    )
    (net (code "11") (name "KL") (class "Default")
      (node (ref "K311") (pin "4") (pinfunction "P_4") (pintype "passive"))
      (node (ref "X321") (pin "1") (pinfunction "1_1") (pintype "passive"))
    )
    (net (code "12") (name "M1") (class "Default")
      (node (ref "K314") (pin "4") (pinfunction "P_4") (pintype "passive"))
      (node (ref "X321") (pin "4") (pinfunction "4_4") (pintype "passive"))
    )
    (net (code "13") (name "M2") (class "Default")
      (node (ref "K315") (pin "4") (pinfunction "P_4") (pintype "passive"))
      (node (ref "X321") (pin "5") (pinfunction "5_5") (pintype "passive"))
    )
    (net (code "14") (name "MP_ADC0") (class "Default")
      (node (ref "C631") (pin "1") (pinfunction "1_1") (pintype "passive"))
      (node (ref "R631") (pin "2") (pinfunction "2_2") (pintype "passive"))
      (node (ref "R632") (pin "1") (pinfunction "1_1") (pintype "passive"))
      (node (ref "U101") (pin "23") (pinfunction "PC0(ADC0)_23") (pintype "bidirectional"))
    )
    (net (code "15") (name "MP_ADC1") (class "Default")
      (node (ref "U101") (pin "24") (pinfunction "PC1(ADC1)_24") (pintype "bidirectional"))
    )
    (net (code "16") (name "MP_AVCC") (class "Default")
      (node (ref "L101") (pin "1") (pinfunction "1_1") (pintype "passive"))
      (node (ref "U101") (pin "20") (pinfunction "AVCC_20") (pintype "bidirectional"))
    )
    (net (code "17") (name "MP_FB") (class "Default")
      (node (ref "R124") (pin "1") (pinfunction "1_1") (pintype "passive"))
      (node (ref "R321") (pin "1") (pinfunction "1_1") (pintype "passive"))
      (node (ref "U101") (pin "14") (pinfunction "PB0(ICP)_14") (pintype "bidirectional"))
    )
    (net (code "18") (name "MP_INT") (class "Default")
      (node (ref "U101") (pin "4") (pinfunction "PD2(INT0)_4") (pintype "bidirectional"))
    )
    (net (code "19") (name "MP_KL") (class "Default")
      (node (ref "R135") (pin "2") (pinfunction "2_2") (pintype "passive"))
      (node (ref "U101") (pin "26") (pinfunction "PC3(ADC3)_26") (pintype "bidirectional"))
      (node (ref "U301") (pin "1") (pinfunction "IN1_1") (pintype "input"))
    )
    (net (code "20") (name "MP_M1") (class "Default")
      (node (ref "R133") (pin "2") (pinfunction "2_2") (pintype "passive"))
      (node (ref "U101") (pin "17") (pinfunction "PB3(MOSI/OC2)_17") (pintype "bidirectional"))
      (node (ref "U301") (pin "4") (pinfunction "IN4_4") (pintype "input"))
    )
    (net (code "21") (name "MP_M2") (class "Default")
      (node (ref "R134") (pin "2") (pinfunction "2_2") (pintype "passive"))
      (node (ref "U101") (pin "16") (pinfunction "PB2(SS/OC1B)_16") (pintype "bidirectional"))
      (node (ref "U301") (pin "5") (pinfunction "IN5_5") (pintype "input"))
    )
    (net (code "22") (name "MP_PV_G") (class "Default")
      (node (ref "R131") (pin "2") (pinfunction "2_2") (pintype "passive"))
      (node (ref "U101") (pin "19") (pinfunction "PB5(SCK)_19") (pintype "bidirectional"))
      (node (ref "U301") (pin "2") (pinfunction "IN2_2") (pintype "input"))
    )
    (net (code "23") (name "MP_PV_O") (class "Default")
      (node (ref "R132") (pin "2") (pinfunction "2_2") (pintype "passive"))
      (node (ref "U101") (pin "18") (pinfunction "PB4(MISO)_18") (pintype "bidirectional"))
      (node (ref "U301") (pin "3") (pinfunction "IN3_3") (pintype "input"))
    )
    (net (code "24") (name "MP_RXD") (class "Default")
      (node (ref "U101") (pin "2") (pinfunction "PD0(RXD)_2") (pintype "bidirectional"))
      (node (ref "U501") (pin "12") (pinfunction "R1OUT_12") (pintype "output"))
    )
    (net (code "25") (name "MP_SA_G") (class "Default")
      (node (ref "R122") (pin "1") (pinfunction "1_1") (pintype "passive"))
      (node (ref "R215") (pin "2") (pinfunction "2_2") (pintype "passive"))
      (node (ref "U101") (pin "12") (pinfunction "PD6(AIN0)_12") (pintype "bidirectional"))
      (node (ref "U221") (pin "2") (pinfunction "C_2") (pintype "passive"))
    )
    (net (code "26") (name "MP_SA_O") (class "Default")
      (node (ref "R123") (pin "1") (pinfunction "1_1") (pintype "passive"))
      (node (ref "R216") (pin "2") (pinfunction "2_2") (pintype "passive"))
      (node (ref "U101") (pin "13") (pinfunction "PD7(AIN1)_13") (pintype "bidirectional"))
      (node (ref "U221") (pin "4") (pinfunction "D_4") (pintype "passive"))
    )
    (net (code "27") (name "MP_SH_G") (class "Default")
      (node (ref "R121") (pin "1") (pinfunction "1_1") (pintype "passive"))
      (node (ref "R212") (pin "2") (pinfunction "2_2") (pintype "passive"))
      (node (ref "U101") (pin "6") (pinfunction "PD4(XCK/T0)_6") (pintype "bidirectional"))
    )
    (net (code "28") (name "MP_SK_G") (class "Default")
      (node (ref "R125") (pin "2") (pinfunction "2_2") (pintype "passive"))
      (node (ref "R213") (pin "2") (pinfunction "2_2") (pintype "passive"))
      (node (ref "U101") (pin "9") (pinfunction "PB6(XTAL1/TOSC1)_9") (pintype "bidirectional"))
      (node (ref "U221") (pin "8") (pinfunction "A_8") (pintype "passive"))
    )
    (net (code "29") (name "MP_SK_O") (class "Default")
      (node (ref "R126") (pin "2") (pinfunction "2_2") (pintype "passive"))
      (node (ref "R214") (pin "2") (pinfunction "2_2") (pintype "passive"))
      (node (ref "U101") (pin "10") (pinfunction "PB7(XTAL2/TOSC2)_10") (pintype "bidirectional"))
      (node (ref "U221") (pin "6") (pinfunction "B_6") (pintype "passive"))
    )
    (net (code "30") (name "MP_TACHO") (class "Default")
      (node (ref "R211") (pin "1") (pinfunction "1_1") (pintype "passive"))
      (node (ref "R231") (pin "2") (pinfunction "2_2") (pintype "passive"))
      (node (ref "U101") (pin "25") (pinfunction "PC2(ADC2)_25") (pintype "bidirectional"))
    )
    (net (code "31") (name "MP_TXD") (class "Default")
      (node (ref "U101") (pin "3") (pinfunction "PD1(TXD)_3") (pintype "bidirectional"))
      (node (ref "U501") (pin "11") (pinfunction "T1IN_11") (pintype "input"))
    )
    (net (code "32") (name "MX_C1P") (class "Default")
      (node (ref "C501") (pin "1") (pinfunction "1_1") (pintype "passive"))
      (node (ref "U501") (pin "1") (pinfunction "C1+_1") (pintype "bidirectional"))
    )
    (net (code "33") (name "MX_C2P") (class "Default")
      (node (ref "C502") (pin "1") (pinfunction "1_1") (pintype "passive"))
      (node (ref "U501") (pin "4") (pinfunction "C2+_4") (pintype "bidirectional"))
    )
    (net (code "34") (name "MX_VM") (class "Default")
      (node (ref "C504") (pin "1") (pinfunction "1_1") (pintype "passive"))
      (node (ref "U501") (pin "6") (pinfunction "V-_6") (pintype "bidirectional"))
    )
    (net (code "35") (name "MX_VP") (class "Default")
      (node (ref "C503") (pin "1") (pinfunction "1_1") (pintype "passive"))
      (node (ref "U501") (pin "2") (pinfunction "V+_2") (pintype "bidirectional"))
    )
    (net (code "36") (name "Net-(D141-PadA)") (class "Default")
      (node (ref "D141") (pin "A") (pinfunction "A_A") (pintype "passive"))
      (node (ref "R141") (pin "2") (pinfunction "2_2") (pintype "passive"))
    )
    (net (code "37") (name "Net-(U101-AREF)") (class "Default")
      (node (ref "C102") (pin "2") (pinfunction "2_2") (pintype "passive"))
      (node (ref "U101") (pin "21") (pinfunction "AREF_21") (pintype "bidirectional"))
    )
    (net (code "38") (name "Net-(U101-PD3(INT1))") (class "Default")
      (node (ref "R141") (pin "1") (pinfunction "1_1") (pintype "passive"))
      (node (ref "U101") (pin "5") (pinfunction "PD3(INT1)_5") (pintype "bidirectional"))
    )
    (net (code "39") (name "Net-(U501A-C1-)") (class "Default")
      (node (ref "C501") (pin "2") (pinfunction "2_2") (pintype "passive"))
      (node (ref "U501") (pin "3") (pinfunction "C1-_3") (pintype "bidirectional"))
    )
    (net (code "40") (name "Net-(U501A-C2-)") (class "Default")
      (node (ref "C502") (pin "2") (pinfunction "2_2") (pintype "passive"))
      (node (ref "U501") (pin "5") (pinfunction "C2-_5") (pintype "bidirectional"))
    )
    (net (code "41") (name "PV_G") (class "Default")
      (node (ref "K312") (pin "4") (pinfunction "P_4") (pintype "passive"))
      (node (ref "X321") (pin "2") (pinfunction "2_2") (pintype "passive"))
    )
    (net (code "42") (name "PV_O") (class "Default")
      (node (ref "K313") (pin "4") (pinfunction "P_4") (pintype "passive"))
      (node (ref "X321") (pin "3") (pinfunction "3_3") (pintype "passive"))
    )
    (net (code "43") (name "REGIN") (class "Default")
      (node (ref "C601") (pin "+") (pinfunction "+_+") (pintype "passive"))
      (node (ref "C602") (pin "1") (pinfunction "1_1") (pintype "passive"))
      (node (ref "D601") (pin "C") (pinfunction "C_C") (pintype "passive"))
      (node (ref "F602") (pin "3") (pinfunction "2_3") (pintype "passive"))
      (node (ref "F602") (pin "4") (pinfunction "2_4") (pintype "passive"))
      (node (ref "IC611") (pin "1") (pinfunction "VI_1") (pintype "input"))
    )
    (net (code "44") (name "RXD") (class "Default")
      (node (ref "U501") (pin "13") (pinfunction "R1IN_13") (pintype "input"))
      (node (ref "X511") (pin "2") (pinfunction "2_2") (pintype "passive"))
    )
    (net (code "45") (name "SA_G") (class "Default")
      (node (ref "R215") (pin "1") (pinfunction "1_1") (pintype "passive"))
      (node (ref "X201") (pin "5") (pinfunction "5_5") (pintype "passive"))
    )
    (net (code "46") (name "SA_O") (class "Default")
      (node (ref "R216") (pin "1") (pinfunction "1_1") (pintype "passive"))
      (node (ref "X201") (pin "6") (pinfunction "6_6") (pintype "passive"))
    )
    (net (code "47") (name "SCL") (class "Default")
      (node (ref "R491") (pin "1") (pinfunction "1_1") (pintype "passive"))
      (node (ref "U101") (pin "28") (pinfunction "PC5(ADC5/SCL)_28") (pintype "bidirectional"))
      (node (ref "X401") (pin "2") (pinfunction "2_2") (pintype "passive"))
    )
    (net (code "48") (name "SDA") (class "Default")
      (node (ref "R492") (pin "1") (pinfunction "1_1") (pintype "passive"))
      (node (ref "U101") (pin "27") (pinfunction "PC4(ADC4/SDA)_27") (pintype "bidirectional"))
      (node (ref "X401") (pin "4") (pinfunction "4_4") (pintype "passive"))
    )
    (net (code "49") (name "SH_G") (class "Default")
      (node (ref "R212") (pin "1") (pinfunction "1_1") (pintype "passive"))
      (node (ref "X201") (pin "2") (pinfunction "2_2") (pintype "passive"))
    )
    (net (code "50") (name "SK_G") (class "Default")
      (node (ref "R213") (pin "1") (pinfunction "1_1") (pintype "passive"))
      (node (ref "X201") (pin "3") (pinfunction "3_3") (pintype "passive"))
    )
    (net (code "51") (name "SK_O") (class "Default")
      (node (ref "R214") (pin "1") (pinfunction "1_1") (pintype "passive"))
      (node (ref "X201") (pin "4") (pinfunction "4_4") (pintype "passive"))
    )
    (net (code "52") (name "TACHO") (class "Default")
      (node (ref "R211") (pin "2") (pinfunction "2_2") (pintype "passive"))
      (node (ref "X201") (pin "1") (pinfunction "1_1") (pintype "passive"))
    )
    (net (code "53") (name "TXD") (class "Default")
      (node (ref "U501") (pin "14") (pinfunction "T1OUT_14") (pintype "output"))
      (node (ref "X511") (pin "1") (pinfunction "1_1") (pintype "passive"))
    )
    (net (code "54") (name "unconnected-(K311B-O-Pad3)") (class "Default")
      (node (ref "K311") (pin "3") (pinfunction "O_3") (pintype "passive"))
    )
    (net (code "55") (name "unconnected-(K312B-O-Pad3)") (class "Default")
      (node (ref "K312") (pin "3") (pinfunction "O_3") (pintype "passive"))
    )
    (net (code "56") (name "unconnected-(K313B-O-Pad3)") (class "Default")
      (node (ref "K313") (pin "3") (pinfunction "O_3") (pintype "passive"))
    )
    (net (code "57") (name "unconnected-(U101-PB1(OC1A)-Pad15)") (class "Default")
      (node (ref "U101") (pin "15") (pinfunction "PB1(OC1A)_15") (pintype "bidirectional"))
    )
    (net (code "58") (name "unconnected-(U101-PD5(T1)-Pad11)") (class "Default")
      (node (ref "U101") (pin "11") (pinfunction "PD5(T1)_11") (pintype "bidirectional"))
    )
    (net (code "59") (name "unconnected-(U301-IN6-Pad6)") (class "Default")
      (node (ref "U301") (pin "6") (pinfunction "IN6_6") (pintype "input"))
    )
    (net (code "60") (name "unconnected-(U301-IN7-Pad7)") (class "Default")
      (node (ref "U301") (pin "7") (pinfunction "IN7_7") (pintype "input"))
    )
    (net (code "61") (name "unconnected-(U301-IN8-Pad8)") (class "Default")
      (node (ref "U301") (pin "8") (pinfunction "IN8_8") (pintype "input"))
    )
    (net (code "62") (name "unconnected-(U301-OUT6-Pad13)") (class "Default")
      (node (ref "U301") (pin "13") (pinfunction "OUT6_13") (pintype "open_collector"))
    )
    (net (code "63") (name "unconnected-(U301-OUT7-Pad12)") (class "Default")
      (node (ref "U301") (pin "12") (pinfunction "OUT7_12") (pintype "open_collector"))
    )
    (net (code "64") (name "unconnected-(U301-OUT8-Pad11)") (class "Default")
      (node (ref "U301") (pin "11") (pinfunction "OUT8_11") (pintype "open_collector"))
    )
    (net (code "65") (name "unconnected-(U501A-R2OUT-Pad9)") (class "Default")
      (node (ref "U501") (pin "9") (pinfunction "R2OUT_9") (pintype "output"))
    )
    (net (code "66") (name "unconnected-(U501A-T2OUT-Pad7)") (class "Default")
      (node (ref "U501") (pin "7") (pinfunction "T2OUT_7") (pintype "output"))
    )
    (net (code "67") (name "unconnected-(X111-Pad1)") (class "Default")
      (node (ref "X111") (pin "1") (pinfunction "1_1") (pintype "passive"))
    )
    (net (code "68") (name "unconnected-(X111-Pad3)") (class "Default")
      (node (ref "X111") (pin "3") (pinfunction "3_3") (pintype "passive"))
    )
    (net (code "69") (name "unconnected-(X111-Pad4)") (class "Default")
      (node (ref "X111") (pin "4") (pinfunction "4_4") (pintype "passive"))
    )
    (net (code "70") (name "unconnected-(X321-Pad6)") (class "Default")
      (node (ref "X321") (pin "6") (pinfunction "6_6") (pintype "passive"))
    )
    (net (code "71") (name "unconnected-(X321-Pad7)") (class "Default")
      (node (ref "X321") (pin "7") (pinfunction "7_7") (pintype "passive"))
    )
    (net (code "72") (name "unconnected-(X401-Pad5)") (class "Default")
      (node (ref "X401") (pin "5") (pinfunction "5_5") (pintype "passive"))
    )
    (net (code "73") (name "unconnected-(X511-Pad3)") (class "Default")
      (node (ref "X511") (pin "3") (pinfunction "3_3") (pintype "passive"))
    )
    (net (code "74") (name "unconnected-(X511-Pad4)") (class "Default")
      (node (ref "X511") (pin "4") (pinfunction "4_4") (pintype "passive"))
    )
    (net (code "75") (name "~{RST}") (class "Default")
      (node (ref "R101") (pin "2") (pinfunction "2_2") (pintype "passive"))
      (node (ref "U101") (pin "1") (pinfunction "PC6(/RESET)_1") (pintype "bidirectional"))
      (node (ref "X111") (pin "5") (pinfunction "5_5") (pintype "passive"))
    )
  )
)
